# LMP848x_Breakout_v1_3.net
KiCad netlist of a schematic drawn in EAGLE
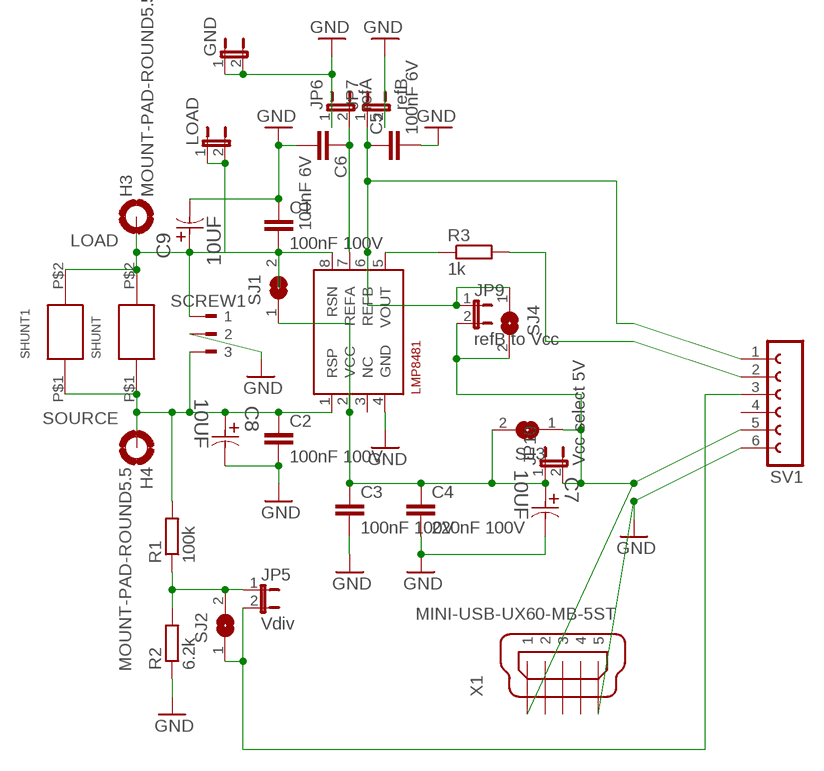
[diagram p0: schematic, sheet 1]

(export (version "E")
  (design (tool "Eeschema 10.0.6"))
  (components
    (comp (ref "C1")
      (value "100nF 100V")
      (footprint "eagle-import:C0805")
      (libsource (lib "eagle-import") (part "C-EUC0805"))
    )
    (comp (ref "C2")
      (value "100nF 100V")
      (footprint "eagle-import:C0805")
      (libsource (lib "eagle-import") (part "C-EUC0805"))
    )
    (comp (ref "C3")
      (value "100nF 100V")
      (footprint "eagle-import:C0805")
      (libsource (lib "eagle-import") (part "C-EUC0805"))
    )
    (comp (ref "C4")
      (value "220nF 100V")
      (footprint "eagle-import:C0805")
      (libsource (lib "eagle-import") (part "C-EUC0805"))
    )
    (comp (ref "C5")
      (value "100nF 6V")
      (footprint "eagle-import:C0805")
      (libsource (lib "eagle-import") (part "C-EUC0805"))
    )
    (comp (ref "C6")
      (value "100nF 6V")
      (footprint "eagle-import:C0805")
      (libsource (lib "eagle-import") (part "C-EUC0805"))
    )
    (comp (ref "C7")
      (value "10UF")
      (footprint "eagle-import:CAPPR250-500X1100")
      (fields (field (name "MPN") "ECA1HM100I") (field (name "TOLERANCE") "±20 %"))
      (libsource (lib "eagle-import") (part "ECA-D5XP2.51HM100I"))
    )
    (comp (ref "C8")
      (value "10UF")
      (footprint "eagle-import:CAPPR250-500X1100")
      (fields (field (name "MPN") "ECA1HM100I") (field (name "TOLERANCE") "±20 %"))
      (libsource (lib "eagle-import") (part "ECA-D5XP2.51HM100I"))
    )
    (comp (ref "C9")
      (value "10UF")
      (footprint "eagle-import:CAPPR250-500X1100")
      (fields (field (name "MPN") "ECA1HM100I") (field (name "TOLERANCE") "±20 %"))
      (libsource (lib "eagle-import") (part "ECA-D5XP2.51HM100I"))
    )
    (comp (ref "GND")
      (value "JP1E")
      (footprint "eagle-import:JP1")
      (libsource (lib "eagle-import") (part "JP1E"))
    )
    (comp (ref "H3")
      (value "MOUNT-PAD-ROUND5.5")
      (footprint "eagle-import:5,5-PAD")
      (libsource (lib "eagle-import") (part "MOUNT-PAD-ROUND5.5"))
    )
    (comp (ref "H4")
      (value "MOUNT-PAD-ROUND5.5")
      (footprint "eagle-import:5,5-PAD")
      (libsource (lib "eagle-import") (part "MOUNT-PAD-ROUND5.5"))
    )
    (comp (ref "JP5")
      (value "Vdiv")
      (footprint "eagle-import:JP1")
      (libsource (lib "eagle-import") (part "JP1E"))
    )
    (comp (ref "JP6")
      (value "refA")
      (footprint "eagle-import:JP1")
      (libsource (lib "eagle-import") (part "JP1E"))
    )
    (comp (ref "JP7")
      (value "refB")
      (footprint "eagle-import:JP1")
      (libsource (lib "eagle-import") (part "JP1E"))
    )
    (comp (ref "JP9")
      (value "refB to Vcc")
      (footprint "eagle-import:JP1")
      (libsource (lib "eagle-import") (part "JP1E"))
    )
    (comp (ref "JP10")
      (value "Vcc select 5V")
      (footprint "eagle-import:JP1")
      (libsource (lib "eagle-import") (part "JP1E"))
    )
    (comp (ref "LMP848X")
      (value "LMP8481-H")
      (footprint "eagle-import:S-PDSO-G08")
      (libsource (lib "eagle-import") (part "LMP8481-H"))
    )
    (comp (ref "LOAD")
      (value "JP1E")
      (footprint "eagle-import:JP1")
      (libsource (lib "eagle-import") (part "JP1E"))
    )
    (comp (ref "R1")
      (value "100k")
      (footprint "eagle-import:0207_7")
      (libsource (lib "eagle-import") (part "R-EU_0207/7"))
    )
    (comp (ref "R2")
      (value "6.2k")
      (footprint "eagle-import:0204_5")
      (libsource (lib "eagle-import") (part "R-EU_0204/5"))
    )
    (comp (ref "R3")
      (value "1k")
      (footprint "eagle-import:0204_5")
      (libsource (lib "eagle-import") (part "R-EU_0204/5"))
    )
    (comp (ref "SCREW1")
      (value "180-3")
      (footprint "eagle-import:180-3")
      (libsource (lib "eagle-import") (part "180-3"))
    )
    (comp (ref "SHUNT")
      (value "EBW_SERIES_15.2MM")
      (footprint "eagle-import:EBW_SERIES_15.2MM")
      (libsource (lib "eagle-import") (part "EBW_SERIES_15.2MM"))
    )
    (comp (ref "SHUNT1")
      (value "EBW_SERIES_15.2MM")
      (footprint "eagle-import:EBW_SERIES_15.2MM")
      (libsource (lib "eagle-import") (part "EBW_SERIES_15.2MM"))
    )
    (comp (ref "SJ1") (value "SJ") (footprint "eagle-import:SJ") (libsource (lib "eagle-import") (part "SJ")))
    (comp (ref "SJ2") (value "SJ") (footprint "eagle-import:SJ") (libsource (lib "eagle-import") (part "SJ")))
    (comp (ref "SJ3") (value "SJ") (footprint "eagle-import:SJ") (libsource (lib "eagle-import") (part "SJ")))
    (comp (ref "SJ4") (value "SJ") (footprint "eagle-import:SJ") (libsource (lib "eagle-import") (part "SJ")))
    (comp (ref "SV1")
      (value "FE06-1")
      (footprint "eagle-import:FE06")
      (libsource (lib "eagle-import") (part "FE06-1"))
    )
    (comp (ref "X1")
      (value "MINI-USB-UX60-MB-5ST")
      (footprint "eagle-import:UX60-MB-5ST")
      (libsource (lib "eagle-import") (part "MINI-USB-UX60-MB-5ST"))
    )
  )
  (nets
    (net (code "1") (name "/LOAD") (class "Default")
      (node (ref "C1") (pin "2") (pinfunction "2_2") (pintype "passive"))
      (node (ref "C9") (pin "1") (pinfunction "1_1") (pintype "passive"))
      (node (ref "H3") (pin "B5,5") (pinfunction "MOUNT_B5,5") (pintype "passive"))
      (node (ref "LMP848X") (pin "8") (pinfunction "RSN_8") (pintype "bidirectional"))
      (node (ref "LOAD") (pin "1") (pinfunction "1_1") (pintype "passive"))
      (node (ref "LOAD") (pin "2") (pinfunction "2_2") (pintype "passive"))
      (node (ref "SCREW1") (pin "1") (pinfunction "1_1") (pintype "passive"))
      (node (ref "SHUNT") (pin "P$2") (pinfunction "P$2_P$2") (pintype "bidirectional"))
      (node (ref "SHUNT1") (pin "P$2") (pinfunction "P$2_P$2") (pintype "bidirectional"))
      (node (ref "SJ1") (pin "2") (pinfunction "2_2") (pintype "passive"))
    )
    (net (code "2") (name "/SOURCE") (class "Default")
      (node (ref "C2") (pin "1") (pinfunction "1_1") (pintype "passive"))
      (node (ref "C8") (pin "1") (pinfunction "1_1") (pintype "passive"))
      (node (ref "H4") (pin "B5,5") (pinfunction "MOUNT_B5,5") (pintype "passive"))
      (node (ref "LMP848X") (pin "1") (pinfunction "RSP_1") (pintype "bidirectional"))
      (node (ref "R1") (pin "2") (pinfunction "2_2") (pintype "passive"))
      (node (ref "SCREW1") (pin "3") (pinfunction "3_3") (pintype "passive"))
      (node (ref "SHUNT") (pin "P$1") (pinfunction "P$1_P$1") (pintype "bidirectional"))
      (node (ref "SHUNT1") (pin "P$1") (pinfunction "P$1_P$1") (pintype "bidirectional"))
    )
    (net (code "3") (name "GND") (class "Default")
      (node (ref "C1") (pin "1") (pinfunction "1_1") (pintype "passive"))
      (node (ref "C2") (pin "2") (pinfunction "2_2") (pintype "passive"))
      (node (ref "C3") (pin "2") (pinfunction "2_2") (pintype "passive"))
      (node (ref "C4") (pin "2") (pinfunction "2_2") (pintype "passive"))
      (node (ref "C5") (pin "2") (pinfunction "2_2") (pintype "passive"))
      (node (ref "C6") (pin "2") (pinfunction "2_2") (pintype "passive"))
      (node (ref "C7") (pin "2") (pinfunction "2_2") (pintype "passive"))
      (node (ref "C8") (pin "2") (pinfunction "2_2") (pintype "passive"))
      (node (ref "C9") (pin "2") (pinfunction "2_2") (pintype "passive"))
      (node (ref "GND") (pin "1") (pinfunction "1_1") (pintype "passive"))
      (node (ref "GND") (pin "2") (pinfunction "2_2") (pintype "passive"))
      (node (ref "JP6") (pin "1") (pinfunction "1_1") (pintype "passive"))
      (node (ref "JP7") (pin "2") (pinfunction "2_2") (pintype "passive"))
      (node (ref "LMP848X") (pin "4") (pinfunction "GND_4") (pintype "bidirectional"))
      (node (ref "R2") (pin "1") (pinfunction "1_1") (pintype "passive"))
      (node (ref "SCREW1") (pin "2") (pinfunction "2_2") (pintype "passive"))
      (node (ref "SV1") (pin "6") (pinfunction "6_6") (pintype "passive"))
      (node (ref "X1") (pin "5") (pinfunction "5_5") (pintype "input"))
    )
    (net (code "4") (name "Net-(JP5-Pad1)") (class "Default")
      (node (ref "JP5") (pin "1") (pinfunction "1_1") (pintype "passive"))
      (node (ref "R1") (pin "1") (pinfunction "1_1") (pintype "passive"))
      (node (ref "R2") (pin "2") (pinfunction "2_2") (pintype "passive"))
      (node (ref "SJ2") (pin "2") (pinfunction "2_2") (pintype "passive"))
    )
    (net (code "5") (name "Net-(JP5-Pad2)") (class "Default")
      (node (ref "JP5") (pin "2") (pinfunction "2_2") (pintype "passive"))
      (node (ref "SJ2") (pin "1") (pinfunction "1_1") (pintype "passive"))
      (node (ref "SV1") (pin "3") (pinfunction "3_3") (pintype "passive"))
    )
    (net (code "6") (name "Net-(JP10-Pad2)") (class "Default")
      (node (ref "JP10") (pin "2") (pinfunction "2_2") (pintype "passive"))
      (node (ref "JP9") (pin "2") (pinfunction "2_2") (pintype "passive"))
      (node (ref "SJ3") (pin "1") (pinfunction "1_1") (pintype "passive"))
      (node (ref "SJ4") (pin "2") (pinfunction "2_2") (pintype "passive"))
      (node (ref "SV1") (pin "5") (pinfunction "5_5") (pintype "passive"))
      (node (ref "X1") (pin "1") (pinfunction "1_1") (pintype "input"))
    )
    (net (code "7") (name "Net-(LMP848X-REFA)") (class "Default")
      (node (ref "C6") (pin "1") (pinfunction "1_1") (pintype "passive"))
      (node (ref "JP6") (pin "2") (pinfunction "2_2") (pintype "passive"))
      (node (ref "LMP848X") (pin "7") (pinfunction "REFA_7") (pintype "bidirectional"))
    )
    (net (code "8") (name "Net-(LMP848X-REFB)") (class "Default")
      (node (ref "C5") (pin "1") (pinfunction "1_1") (pintype "passive"))
      (node (ref "JP7") (pin "1") (pinfunction "1_1") (pintype "passive"))
      (node (ref "JP9") (pin "1") (pinfunction "1_1") (pintype "passive"))
      (node (ref "LMP848X") (pin "6") (pinfunction "REFB_6") (pintype "bidirectional"))
      (node (ref "SJ4") (pin "1") (pinfunction "1_1") (pintype "passive"))
      (node (ref "SV1") (pin "1") (pinfunction "1_1") (pintype "passive"))
    )
    (net (code "9") (name "Net-(LMP848X-VCC)") (class "Default")
      (node (ref "C3") (pin "1") (pinfunction "1_1") (pintype "passive"))
      (node (ref "C4") (pin "1") (pinfunction "1_1") (pintype "passive"))
      (node (ref "C7") (pin "1") (pinfunction "1_1") (pintype "passive"))
      (node (ref "JP10") (pin "1") (pinfunction "1_1") (pintype "passive"))
      (node (ref "LMP848X") (pin "2") (pinfunction "VCC_2") (pintype "bidirectional"))
      (node (ref "SJ1") (pin "1") (pinfunction "1_1") (pintype "passive"))
      (node (ref "SJ3") (pin "2") (pinfunction "2_2") (pintype "passive"))
    )
    (net (code "10") (name "Net-(LMP848X-VOUT)") (class "Default")
      (node (ref "LMP848X") (pin "5") (pinfunction "VOUT_5") (pintype "bidirectional"))
      (node (ref "R3") (pin "1") (pinfunction "1_1") (pintype "passive"))
    )
    (net (code "11") (name "Net-(R3-Pad2)") (class "Default")
      (node (ref "R3") (pin "2") (pinfunction "2_2") (pintype "passive"))
      (node (ref "SV1") (pin "2") (pinfunction "2_2") (pintype "passive"))
    )
    (net (code "12") (name "unconnected-(LMP848X-NC-Pad3)") (class "Default")
      (node (ref "LMP848X") (pin "3") (pinfunction "NC_3") (pintype "bidirectional"))
    )
    (net (code "13") (name "unconnected-(SV1-Pad4)") (class "Default")
      (node (ref "SV1") (pin "4") (pinfunction "4_4") (pintype "passive"))
    )
    (net (code "14") (name "unconnected-(X1-Pad2)") (class "Default")
      (node (ref "X1") (pin "2") (pinfunction "2_2") (pintype "input"))
    )
    (net (code "15") (name "unconnected-(X1-Pad3)") (class "Default")
      (node (ref "X1") (pin "3") (pinfunction "3_3") (pintype "input"))
    )
    (net (code "16") (name "unconnected-(X1-Pad4)") (class "Default")
      (node (ref "X1") (pin "4") (pinfunction "4_4") (pintype "input"))
    )
  )
)
